# Welcome_to_the_Resistance.net
KiCad netlist of a schematic drawn in EAGLE
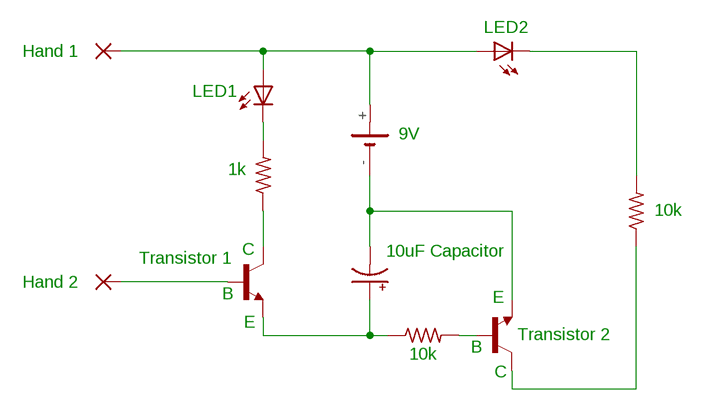
[diagram p0: schematic, sheet 1]

(export (version "E")
  (design (tool "Eeschema 10.0.6"))
  (components
    (comp (ref "C1")
      (value "CPOL-US085CS-1AR")
      (footprint "eagle-import:085CS_1AR")
      (libsource (lib "eagle-import") (part "CPOL-US085CS-1AR"))
    )
    (comp (ref "G1")
      (value "SL-150-1/2AA/PR")
      (footprint "eagle-import:SL-150-1_2AA_PR")
      (libsource (lib "eagle-import") (part "SL-150-1/2AA/PR"))
    )
    (comp (ref "LED1")
      (value "LAP4-BOTTOM")
      (footprint "eagle-import:P47F-BOTTOM")
      (libsource (lib "eagle-import") (part "P4-BOTTOMLA"))
    )
    (comp (ref "LED2")
      (value "LAP4-BOTTOM")
      (footprint "eagle-import:P47F-BOTTOM")
      (libsource (lib "eagle-import") (part "P4-BOTTOMLA"))
    )
    (comp (ref "PAD1")
      (value "2,54/0,8")
      (footprint "eagle-import:2,54_0,8")
      (libsource (lib "eagle-import") (part "2,54/0,8"))
    )
    (comp (ref "PAD2")
      (value "2,54/0,8")
      (footprint "eagle-import:2,54_0,8")
      (libsource (lib "eagle-import") (part "2,54/0,8"))
    )
    (comp (ref "R1")
      (value "R-US_0204/2V")
      (footprint "eagle-import:0204V")
      (libsource (lib "eagle-import") (part "R-US_0204/2V"))
    )
    (comp (ref "R2")
      (value "R-US_0204/2V")
      (footprint "eagle-import:0204V")
      (libsource (lib "eagle-import") (part "R-US_0204/2V"))
    )
    (comp (ref "R3")
      (value "R-US_0204/2V")
      (footprint "eagle-import:0204V")
      (libsource (lib "eagle-import") (part "R-US_0204/2V"))
    )
    (comp (ref "T1")
      (value "2N706")
      (footprint "eagle-import:TO18")
      (libsource (lib "eagle-import") (part "2N706"))
    )
    (comp (ref "T2")
      (value "2N706")
      (footprint "eagle-import:TO18")
      (libsource (lib "eagle-import") (part "2N706"))
    )
  )
  (nets
    (net (code "1") (name "Net-(LED1-PadC)") (class "Default")
      (node (ref "LED1") (pin "C") (pinfunction "C_C") (pintype "passive"))
      (node (ref "R3") (pin "2") (pinfunction "2_2") (pintype "passive"))
    )
    (net (code "2") (name "Net-(LED2-PadC)") (class "Default")
      (node (ref "LED2") (pin "C") (pinfunction "C_C") (pintype "passive"))
      (node (ref "R2") (pin "2") (pinfunction "2_2") (pintype "passive"))
    )
    (net (code "3") (name "Net-(PAD1-P)") (class "Default")
      (node (ref "G1") (pin "+") (pinfunction "+_+") (pintype "passive"))
      (node (ref "LED1") (pin "A") (pinfunction "A_A") (pintype "passive"))
      (node (ref "LED2") (pin "A") (pinfunction "A_A") (pintype "passive"))
      (node (ref "PAD1") (pin "1") (pinfunction "P_1") (pintype "passive"))
    )
    (net (code "4") (name "Net-(PAD2-P)") (class "Default")
      (node (ref "PAD2") (pin "1") (pinfunction "P_1") (pintype "passive"))
      (node (ref "T1") (pin "2") (pinfunction "B_2") (pintype "passive"))
    )
    (net (code "5") (name "Net-(T1-C)") (class "Default")
      (node (ref "R3") (pin "1") (pinfunction "1_1") (pintype "passive"))
      (node (ref "T1") (pin "3") (pinfunction "C_3") (pintype "passive"))
    )
    (net (code "6") (name "Net-(T1-E)") (class "Default")
      (node (ref "C1") (pin "+") (pinfunction "+_+") (pintype "passive"))
      (node (ref "R1") (pin "1") (pinfunction "1_1") (pintype "passive"))
      (node (ref "T1") (pin "1") (pinfunction "E_1") (pintype "passive"))
    )
    (net (code "7") (name "Net-(T2-B)") (class "Default")
      (node (ref "R1") (pin "2") (pinfunction "2_2") (pintype "passive"))
      (node (ref "T2") (pin "2") (pinfunction "B_2") (pintype "passive"))
    )
    (net (code "8") (name "Net-(T2-C)") (class "Default")
      (node (ref "R2") (pin "1") (pinfunction "1_1") (pintype "passive"))
      (node (ref "T2") (pin "3") (pinfunction "C_3") (pintype "passive"))
    )
    (net (code "9") (name "Net-(T2-E)") (class "Default")
      (node (ref "C1") (pin "-") (pinfunction "-_-") (pintype "passive"))
      (node (ref "G1") (pin "-") (pinfunction "-_-") (pintype "passive"))
      (node (ref "T2") (pin "1") (pinfunction "E_1") (pintype "passive"))
    )
  )
)
